# PG04_SHEET2.net
KiCad netlist of a schematic drawn in Altium Designer
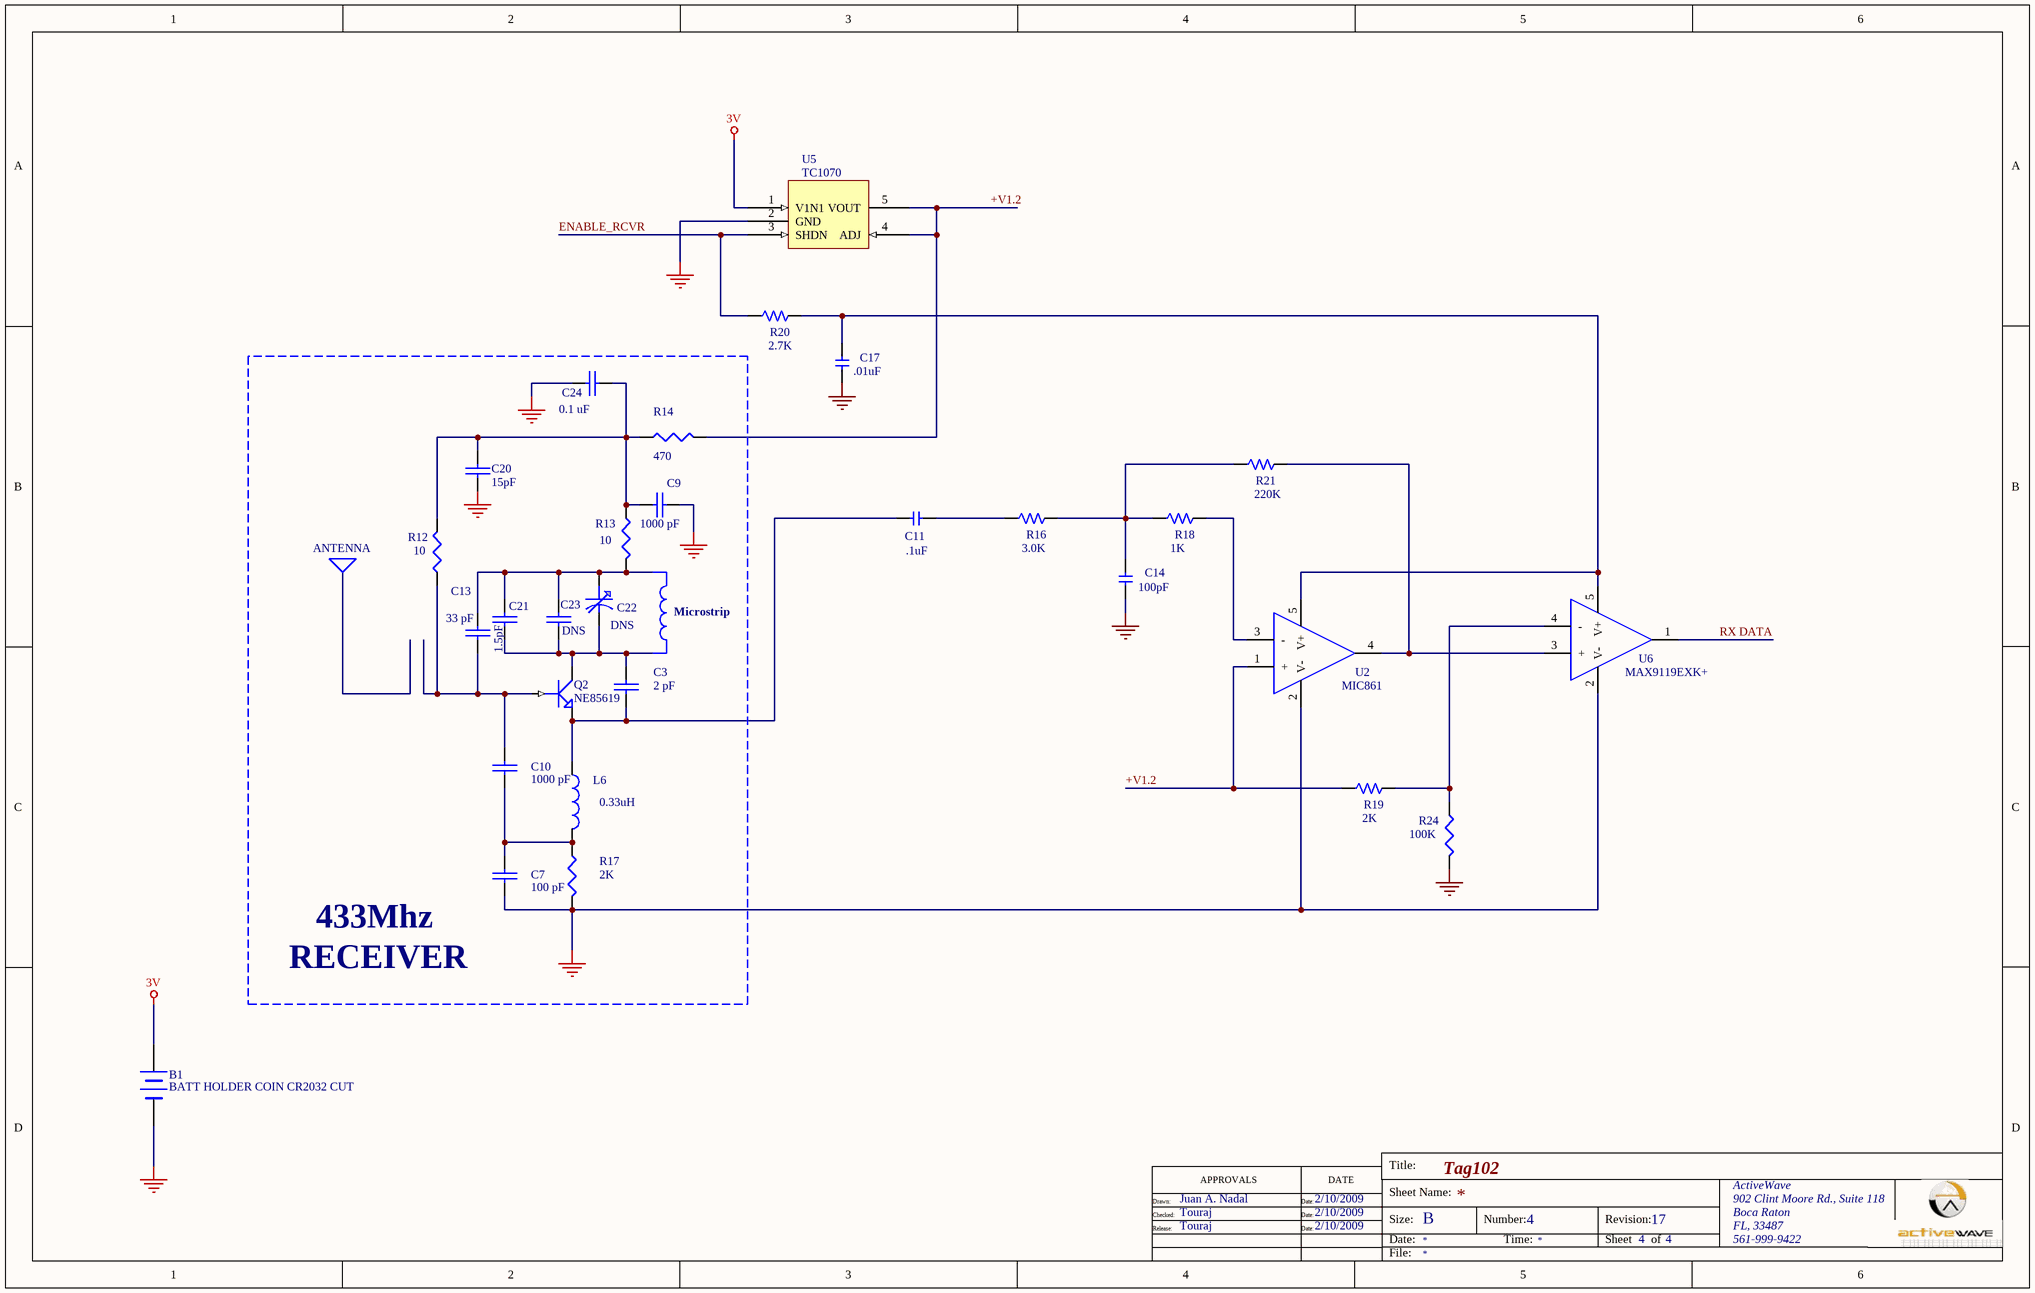
[diagram p0: PG04 SHEET2.schdoc]

(export (version "E")
  (design (tool "Eeschema 10.0.6"))
  (components
    (comp (ref "B1")
      (value "BATT HOLDER COIN CR2032 CUT")
      (footprint "BATT HOLDER COIN CR2032 CUT")
      (description "Battery")
      (libsource (lib "*") (part "BATTERY"))
    )
    (comp (ref "C3")
      (value "2 pF")
      (footprint "0603")
      (description "Capacitor")
      (libsource (lib "*") (part "CAP"))
    )
    (comp (ref "C7")
      (value "100 pF")
      (footprint "0603")
      (description "Capacitor")
      (libsource (lib "*") (part "CAP"))
    )
    (comp (ref "C9")
      (value "1000 pF")
      (footprint "0603")
      (description "Capacitor")
      (libsource (lib "*") (part "CAP"))
    )
    (comp (ref "C10")
      (value "1000 pF")
      (footprint "0603")
      (description "Capacitor")
      (libsource (lib "*") (part "CAP"))
    )
    (comp (ref "C11") (value ".1uF") (footprint "0603") (libsource (lib "*") (part "C")))
    (comp (ref "C13")
      (value "33 pF")
      (footprint "0603")
      (description "Capacitor")
      (libsource (lib "*") (part "CAP"))
    )
    (comp (ref "C14") (value "100pF") (footprint "0603") (libsource (lib "*") (part "C")))
    (comp (ref "C17") (value ".01uF") (footprint "0603") (libsource (lib "*") (part "C")))
    (comp (ref "C20")
      (value "15pF")
      (footprint "0603")
      (description "Capacitor")
      (libsource (lib "*") (part "CAP"))
    )
    (comp (ref "C21")
      (value "1.5pF")
      (footprint "0603")
      (description "Capacitor")
      (libsource (lib "*") (part "CAP"))
    )
    (comp (ref "C22") (value "DNS") (footprint "0603") (libsource (lib "*") (part "CAPACITOR VAR")))
    (comp (ref "C23")
      (value "DNS")
      (footprint "0603")
      (description "Capacitor")
      (libsource (lib "*") (part "CAP"))
    )
    (comp (ref "C24")
      (value "0.1 uF")
      (footprint "0603")
      (description "Capacitor")
      (libsource (lib "*") (part "CAP"))
    )
    (comp (ref "L6") (value "0.33uH") (footprint "0603") (libsource (lib "*") (part "INDUCTOR")))
    (comp (ref "Q2")
      (value "NE85619")
      (footprint "3 PIN ULTRA SUPER MINI MOLD")
      (description "NPN Transistor")
      (libsource (lib "*") (part "NPN1"))
    )
    (comp (ref "R12") (value "10") (footprint "0603") (libsource (lib "") (part "R_1")))
    (comp (ref "R13") (value "10") (footprint "0603") (libsource (lib "") (part "R_1")))
    (comp (ref "R14") (value "470") (footprint "0603") (libsource (lib "") (part "R_1")))
    (comp (ref "R16") (value "3.0K") (footprint "0603") (libsource (lib "*") (part "R")))
    (comp (ref "R17") (value "2K") (footprint "0603") (libsource (lib "*") (part "RESISTOR")))
    (comp (ref "R18") (value "1K") (footprint "0603") (libsource (lib "*") (part "R")))
    (comp (ref "R19") (value "2K") (footprint "0603") (libsource (lib "*") (part "R")))
    (comp (ref "R20") (value "2.7K") (footprint "0603") (libsource (lib "*") (part "R")))
    (comp (ref "R21") (value "220K") (footprint "0603") (libsource (lib "*") (part "R")))
    (comp (ref "R24") (value "100K") (footprint "0603") (libsource (lib "") (part "R_1")))
    (comp (ref "U2") (value "MIC861") (libsource (lib "*") (part "OPAMP MIC861")))
    (comp (ref "U5") (value "TC1070") (footprint "SOT23-5A") (libsource (lib "*") (part "TC1070-2")))
    (comp (ref "U6")
      (value "MAX9119EXK+")
      (footprint "SC70")
      (libsource (lib "*") (part "COMPARATOR MAX9117"))
    )
  )
  (nets
    (net (code "1") (name "/+V1.2") (class "Default")
      (node (ref "R14") (pin "2") (pinfunction "2_2") (pintype "passive"))
      (node (ref "R19") (pin "1") (pinfunction "1_1") (pintype "passive"))
      (node (ref "U2") (pin "1") (pinfunction "+_1") (pintype "passive"))
      (node (ref "U5") (pin "4") (pinfunction "ADJ_4") (pintype "input"))
      (node (ref "U5") (pin "5") (pinfunction "VOUT_5") (pintype "power_in"))
    )
    (net (code "2") (name "/ENABLE_RCVR") (class "Default")
      (node (ref "R20") (pin "1") (pinfunction "1_1") (pintype "passive"))
      (node (ref "U5") (pin "3") (pinfunction "SHDN_3") (pintype "input"))
    )
    (net (code "3") (name "/RX DATA") (class "Default")
      (node (ref "U6") (pin "1") (pinfunction "OUT_1") (pintype "passive"))
    )
    (net (code "4") (name "3V") (class "Default")
      (node (ref "B1") (pin "2") (pinfunction "+_2") (pintype "passive"))
      (node (ref "U5") (pin "1") (pinfunction "V1N1_1") (pintype "input"))
    )
    (net (code "5") (name "GND") (class "Default")
      (node (ref "B1") (pin "1") (pinfunction "-_1") (pintype "passive"))
      (node (ref "C14") (pin "1") (pinfunction "1_1") (pintype "passive"))
      (node (ref "C17") (pin "1") (pinfunction "1_1") (pintype "passive"))
      (node (ref "C20") (pin "1") (pinfunction "1_1") (pintype "passive"))
      (node (ref "C24") (pin "1") (pinfunction "1_1") (pintype "passive"))
      (node (ref "C7") (pin "2") (pinfunction "2_2") (pintype "passive"))
      (node (ref "C9") (pin "2") (pinfunction "2_2") (pintype "passive"))
      (node (ref "R17") (pin "2") (pinfunction "2_2") (pintype "passive"))
      (node (ref "R24") (pin "2") (pinfunction "2_2") (pintype "passive"))
      (node (ref "U2") (pin "2") (pinfunction "V-_2") (pintype "passive"))
      (node (ref "U5") (pin "2") (pinfunction "GND_2") (pintype "power_in"))
      (node (ref "U6") (pin "2") (pinfunction "V-_2") (pintype "passive"))
    )
    (net (code "6") (name "Net-(C10-Pad1)") (class "Default")
      (node (ref "C10") (pin "1") (pinfunction "1_1") (pintype "passive"))
      (node (ref "C13") (pin "1") (pinfunction "1_1") (pintype "passive"))
      (node (ref "Q2") (pin "B") (pinfunction "B_B") (pintype "input"))
      (node (ref "R12") (pin "1") (pinfunction "1_1") (pintype "passive"))
    )
    (net (code "7") (name "Net-(C10-Pad2)") (class "Default")
      (node (ref "C10") (pin "2") (pinfunction "2_2") (pintype "passive"))
      (node (ref "C7") (pin "1") (pinfunction "1_1") (pintype "passive"))
      (node (ref "L6") (pin "2") (pinfunction "2_2") (pintype "passive"))
      (node (ref "R17") (pin "1") (pinfunction "1_1") (pintype "passive"))
    )
    (net (code "8") (name "Net-(C11-Pad1)") (class "Default")
      (node (ref "C11") (pin "1") (pinfunction "1_1") (pintype "passive"))
      (node (ref "C3") (pin "2") (pinfunction "2_2") (pintype "passive"))
      (node (ref "L6") (pin "1") (pinfunction "1_1") (pintype "passive"))
      (node (ref "Q2") (pin "E") (pinfunction "E_E") (pintype "passive"))
    )
    (net (code "9") (name "Net-(C11-Pad2)") (class "Default")
      (node (ref "C11") (pin "2") (pinfunction "2_2") (pintype "passive"))
      (node (ref "R16") (pin "1") (pinfunction "1_1") (pintype "passive"))
    )
    (net (code "10") (name "Net-(C13-Pad2)") (class "Default")
      (node (ref "C13") (pin "2") (pinfunction "2_2") (pintype "passive"))
      (node (ref "C21") (pin "1") (pinfunction "1_1") (pintype "passive"))
      (node (ref "C22") (pin "1") (pinfunction "1_1") (pintype "passive"))
      (node (ref "C23") (pin "1") (pinfunction "1_1") (pintype "passive"))
      (node (ref "R13") (pin "2") (pinfunction "2_2") (pintype "passive"))
    )
    (net (code "11") (name "Net-(C14-Pad2)") (class "Default")
      (node (ref "C14") (pin "2") (pinfunction "2_2") (pintype "passive"))
      (node (ref "R16") (pin "2") (pinfunction "2_2") (pintype "passive"))
      (node (ref "R18") (pin "1") (pinfunction "1_1") (pintype "passive"))
      (node (ref "R21") (pin "1") (pinfunction "1_1") (pintype "passive"))
    )
    (net (code "12") (name "Net-(C20-Pad2)") (class "Default")
      (node (ref "C20") (pin "2") (pinfunction "2_2") (pintype "passive"))
      (node (ref "C24") (pin "2") (pinfunction "2_2") (pintype "passive"))
      (node (ref "C9") (pin "1") (pinfunction "1_1") (pintype "passive"))
      (node (ref "R12") (pin "2") (pinfunction "2_2") (pintype "passive"))
      (node (ref "R13") (pin "1") (pinfunction "1_1") (pintype "passive"))
      (node (ref "R14") (pin "1") (pinfunction "1_1") (pintype "passive"))
    )
    (net (code "13") (name "Net-(C21-Pad2)") (class "Default")
      (node (ref "C21") (pin "2") (pinfunction "2_2") (pintype "passive"))
      (node (ref "C22") (pin "2") (pinfunction "2_2") (pintype "passive"))
      (node (ref "C23") (pin "2") (pinfunction "2_2") (pintype "passive"))
      (node (ref "C3") (pin "1") (pinfunction "1_1") (pintype "passive"))
      (node (ref "Q2") (pin "C") (pinfunction "C_C") (pintype "passive"))
    )
    (net (code "14") (name "Net-(U2--)") (class "Default")
      (node (ref "R18") (pin "2") (pinfunction "2_2") (pintype "passive"))
      (node (ref "U2") (pin "3") (pinfunction "-_3") (pintype "passive"))
    )
    (net (code "15") (name "Net-(U2-OUT)") (class "Default")
      (node (ref "R21") (pin "2") (pinfunction "2_2") (pintype "passive"))
      (node (ref "U2") (pin "4") (pinfunction "OUT_4") (pintype "passive"))
      (node (ref "U6") (pin "3") (pinfunction "+_3") (pintype "passive"))
    )
    (net (code "16") (name "Net-(U2-V+)") (class "Default")
      (node (ref "C17") (pin "2") (pinfunction "2_2") (pintype "passive"))
      (node (ref "R20") (pin "2") (pinfunction "2_2") (pintype "passive"))
      (node (ref "U2") (pin "5") (pinfunction "V+_5") (pintype "passive"))
      (node (ref "U6") (pin "5") (pinfunction "V+_5") (pintype "passive"))
    )
    (net (code "17") (name "Net-(U6--)") (class "Default")
      (node (ref "R19") (pin "2") (pinfunction "2_2") (pintype "passive"))
      (node (ref "R24") (pin "1") (pinfunction "1_1") (pintype "passive"))
      (node (ref "U6") (pin "4") (pinfunction "-_4") (pintype "passive"))
    )
  )
)
